# Schematic.net
KiCad netlist of a schematic drawn in Altium Designer
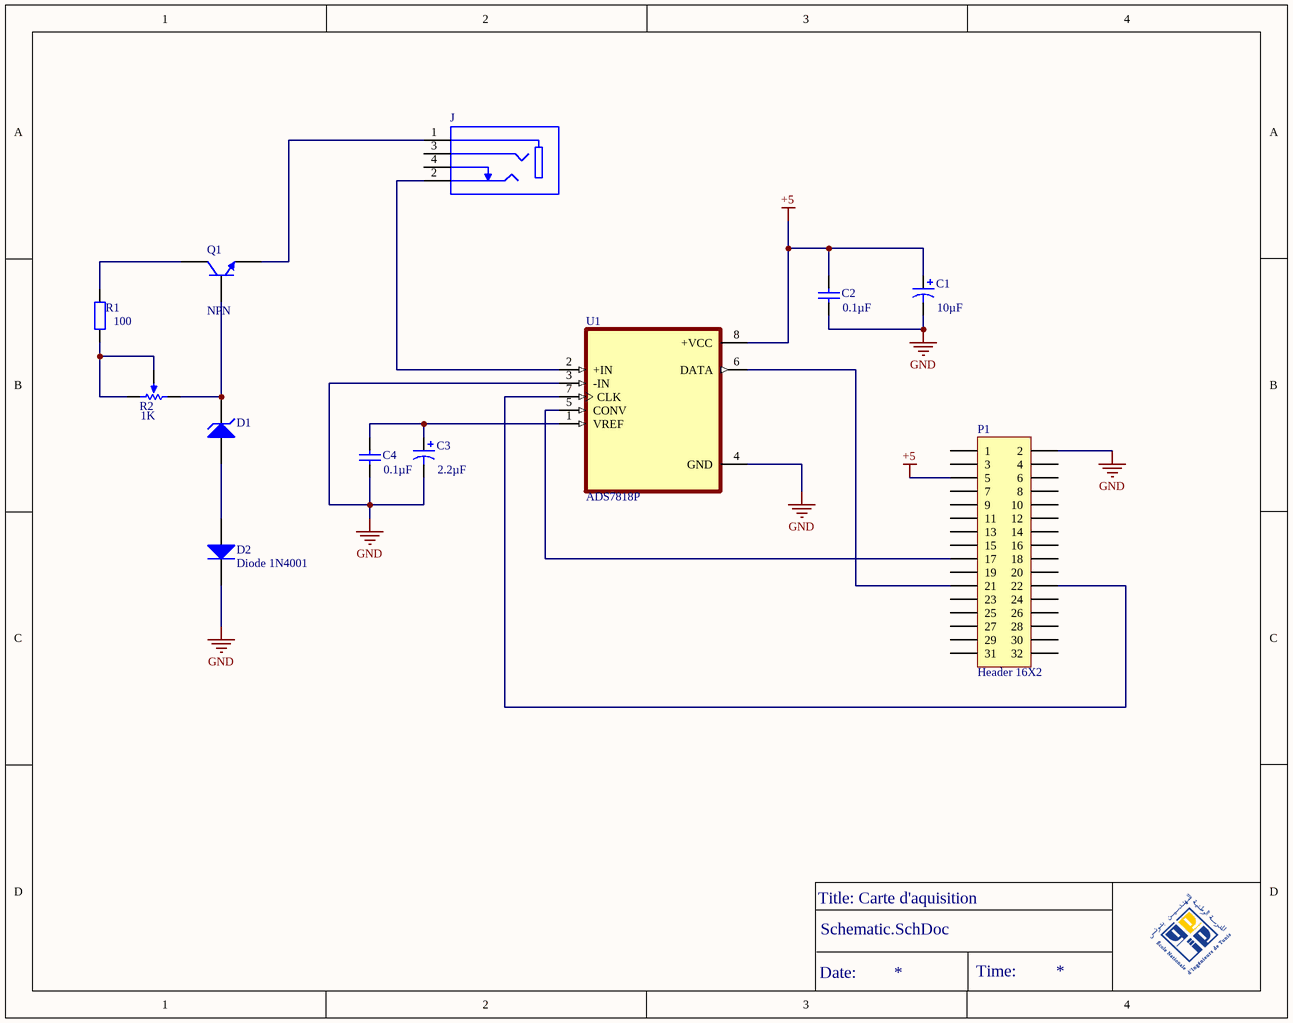
[diagram p0: Schematic.SchDoc]

(export (version "E")
  (design (tool "Eeschema 10.0.6"))
  (components
    (comp (ref "C1")
      (value "10µF")
      (footprint "RB7.6-15")
      (description "Polarized Capacitor (Radial)")
      (fields (field (name "Comment") "Cap Pol1") (field (name "PUBLISHER") "Altium Limited"))
      (libsource (lib "Miscellaneous Devices") (part "Cap Pol1"))
    )
    (comp (ref "C2")
      (value "0.1µF")
      (footprint "RAD-0.3")
      (description "Capacitor")
      (fields (field (name "Comment") "Cap") (field (name "PUBLISHER") "Altium Limited"))
      (libsource (lib "Miscellaneous Devices") (part "Cap"))
    )
    (comp (ref "C3")
      (value "2.2µF")
      (footprint "RB7.6-15")
      (description "Polarized Capacitor (Radial)")
      (fields (field (name "Comment") "Cap Pol1") (field (name "PUBLISHER") "Altium Limited"))
      (libsource (lib "Miscellaneous Devices") (part "Cap Pol1"))
    )
    (comp (ref "C4")
      (value "0.1µF")
      (footprint "RAD-0.3")
      (description "Capacitor")
      (fields (field (name "Comment") "Cap") (field (name "PUBLISHER") "Altium Limited"))
      (libsource (lib "Miscellaneous Devices") (part "Cap"))
    )
    (comp (ref "D1")
      (value "D Zener")
      (footprint "DIODE-0.7")
      (description "Zener Diode")
      (fields (field (name "PUBLISHER") "Altium Limited"))
      (libsource (lib "Miscellaneous Devices") (part "D Zener"))
    )
    (comp (ref "D2")
      (value "Diode 1N4001")
      (footprint "DO-41")
      (description "1 Amp General Purpose Rectifier")
      (fields (field (name "PUBLISHER") "Altium Limited"))
      (libsource (lib "Miscellaneous Devices") (part "Diode 1N4001"))
    )
    (comp (ref "J")
      (value "SJ1-3534N")
      (footprint "CUI_SJ1-3534N")
      (fields (field (name "MF") "CUI Devices"))
      (libsource (lib "SnapEDAsch") (part "SJ1-3534N"))
    )
    (comp (ref "P1")
      (value "Header 16X2")
      (footprint "HDR2X16")
      (description "Header, 16-Pin, Dual row")
      (fields (field (name "PUBLISHER") "Altium Limited"))
      (libsource (lib "Miscellaneous Connectors") (part "Header 16X2"))
    )
    (comp (ref "Q1")
      (value "NPN")
      (footprint "TO-226-AA")
      (description "NPN Bipolar Transistor")
      (fields (field (name "PUBLISHER") "Altium Limited"))
      (libsource (lib "Miscellaneous Devices") (part "NPN"))
    )
    (comp (ref "R1")
      (value "100")
      (footprint "AXIAL-0.4")
      (description "Resistor")
      (fields (field (name "Comment") "Res2"))
      (libsource (lib "Custom_Component") (part "Res2"))
    )
    (comp (ref "R2")
      (value "1K")
      (footprint "VR5")
      (description "Potentiometer")
      (fields (field (name "Comment") "RPot"))
      (libsource (lib "Custom_Component") (part "RPot"))
    )
    (comp (ref "U1")
      (value "ADS7818P")
      (footprint "DIP794W45P254L959H508Q8")
      (libsource (lib "ADS7818P") (part "ADS7818P"))
    )
  )
  (nets
    (net (code "1") (name "+5") (class "Default")
      (node (ref "C1") (pin "1") (pinfunction "1_1") (pintype "passive"))
      (node (ref "C2") (pin "2") (pinfunction "2_2") (pintype "passive"))
      (node (ref "P1") (pin "5") (pinfunction "5_5") (pintype "passive"))
      (node (ref "U1") (pin "8") (pinfunction "+VCC_8") (pintype "power_in"))
    )
    (net (code "2") (name "GND") (class "Default")
      (node (ref "C1") (pin "2") (pinfunction "2_2") (pintype "passive"))
      (node (ref "C2") (pin "1") (pinfunction "1_1") (pintype "passive"))
      (node (ref "C3") (pin "2") (pinfunction "2_2") (pintype "passive"))
      (node (ref "C4") (pin "1") (pinfunction "1_1") (pintype "passive"))
      (node (ref "D2") (pin "2") (pinfunction "K_2") (pintype "passive"))
      (node (ref "P1") (pin "2") (pinfunction "2_2") (pintype "passive"))
      (node (ref "U1") (pin "3") (pinfunction "-IN_3") (pintype "input"))
      (node (ref "U1") (pin "4") (pinfunction "GND_4") (pintype "power_in"))
    )
    (net (code "3") (name "Net-(D1-A)") (class "Default")
      (node (ref "D1") (pin "1") (pinfunction "A_1") (pintype "passive"))
      (node (ref "D2") (pin "1") (pinfunction "A_1") (pintype "passive"))
    )
    (net (code "4") (name "Net-(D1-K)") (class "Default")
      (node (ref "D1") (pin "2") (pinfunction "K_2") (pintype "passive"))
      (node (ref "Q1") (pin "2") (pinfunction "B_2") (pintype "passive"))
      (node (ref "R2") (pin "1") (pinfunction "TOP_1") (pintype "passive"))
    )
    (net (code "5") (name "Net-(Q1-C)") (class "Default")
      (node (ref "Q1") (pin "1") (pinfunction "C_1") (pintype "passive"))
      (node (ref "R1") (pin "2") (pinfunction "2_2") (pintype "passive"))
    )
    (net (code "6") (name "Net-(Q1-E)") (class "Default")
      (node (ref "J") (pin "1") (pinfunction "1_1") (pintype "passive"))
      (node (ref "Q1") (pin "3") (pinfunction "E_3") (pintype "passive"))
    )
    (net (code "7") (name "Net-(R2-BOT)") (class "Default")
      (node (ref "R1") (pin "1") (pinfunction "1_1") (pintype "passive"))
      (node (ref "R2") (pin "2") (pinfunction "BOT_2") (pintype "passive"))
      (node (ref "R2") (pin "3") (pinfunction "TAP_3") (pintype "passive"))
    )
    (net (code "8") (name "Net-(U1-+IN)") (class "Default")
      (node (ref "J") (pin "2") (pinfunction "2_2") (pintype "passive"))
      (node (ref "U1") (pin "2") (pinfunction "+IN_2") (pintype "input"))
    )
    (net (code "9") (name "Net-(U1-CLK)") (class "Default")
      (node (ref "P1") (pin "22") (pinfunction "22_22") (pintype "passive"))
      (node (ref "U1") (pin "7") (pinfunction "CLK_7") (pintype "input"))
    )
    (net (code "10") (name "Net-(U1-CONV)") (class "Default")
      (node (ref "P1") (pin "17") (pinfunction "17_17") (pintype "passive"))
      (node (ref "U1") (pin "5") (pinfunction "CONV_5") (pintype "input"))
    )
    (net (code "11") (name "Net-(U1-DATA)") (class "Default")
      (node (ref "P1") (pin "21") (pinfunction "21_21") (pintype "passive"))
      (node (ref "U1") (pin "6") (pinfunction "DATA_6") (pintype "output"))
    )
    (net (code "12") (name "Net-(U1-VREF)") (class "Default")
      (node (ref "C3") (pin "1") (pinfunction "1_1") (pintype "passive"))
      (node (ref "C4") (pin "2") (pinfunction "2_2") (pintype "passive"))
      (node (ref "U1") (pin "1") (pinfunction "VREF_1") (pintype "input"))
    )
    (net (code "13") (name "unconnected-(J-Pad3)") (class "Default")
      (node (ref "J") (pin "3") (pinfunction "3_3") (pintype "passive"))
    )
    (net (code "14") (name "unconnected-(J-Pad4)") (class "Default")
      (node (ref "J") (pin "4") (pinfunction "4_4") (pintype "passive"))
    )
    (net (code "15") (name "unconnected-(P1-Pad1)") (class "Default")
      (node (ref "P1") (pin "1") (pinfunction "1_1") (pintype "passive"))
    )
    (net (code "16") (name "unconnected-(P1-Pad3)") (class "Default")
      (node (ref "P1") (pin "3") (pinfunction "3_3") (pintype "passive"))
    )
    (net (code "17") (name "unconnected-(P1-Pad4)") (class "Default")
      (node (ref "P1") (pin "4") (pinfunction "4_4") (pintype "passive"))
    )
    (net (code "18") (name "unconnected-(P1-Pad6)") (class "Default")
      (node (ref "P1") (pin "6") (pinfunction "6_6") (pintype "passive"))
    )
    (net (code "19") (name "unconnected-(P1-Pad7)") (class "Default")
      (node (ref "P1") (pin "7") (pinfunction "7_7") (pintype "passive"))
    )
    (net (code "20") (name "unconnected-(P1-Pad8)") (class "Default")
      (node (ref "P1") (pin "8") (pinfunction "8_8") (pintype "passive"))
    )
    (net (code "21") (name "unconnected-(P1-Pad9)") (class "Default")
      (node (ref "P1") (pin "9") (pinfunction "9_9") (pintype "passive"))
    )
    (net (code "22") (name "unconnected-(P1-Pad10)") (class "Default")
      (node (ref "P1") (pin "10") (pinfunction "10_10") (pintype "passive"))
    )
    (net (code "23") (name "unconnected-(P1-Pad11)") (class "Default")
      (node (ref "P1") (pin "11") (pinfunction "11_11") (pintype "passive"))
    )
    (net (code "24") (name "unconnected-(P1-Pad12)") (class "Default")
      (node (ref "P1") (pin "12") (pinfunction "12_12") (pintype "passive"))
    )
    (net (code "25") (name "unconnected-(P1-Pad13)") (class "Default")
      (node (ref "P1") (pin "13") (pinfunction "13_13") (pintype "passive"))
    )
    (net (code "26") (name "unconnected-(P1-Pad14)") (class "Default")
      (node (ref "P1") (pin "14") (pinfunction "14_14") (pintype "passive"))
    )
    (net (code "27") (name "unconnected-(P1-Pad15)") (class "Default")
      (node (ref "P1") (pin "15") (pinfunction "15_15") (pintype "passive"))
    )
    (net (code "28") (name "unconnected-(P1-Pad16)") (class "Default")
      (node (ref "P1") (pin "16") (pinfunction "16_16") (pintype "passive"))
    )
    (net (code "29") (name "unconnected-(P1-Pad18)") (class "Default")
      (node (ref "P1") (pin "18") (pinfunction "18_18") (pintype "passive"))
    )
    (net (code "30") (name "unconnected-(P1-Pad19)") (class "Default")
      (node (ref "P1") (pin "19") (pinfunction "19_19") (pintype "passive"))
    )
    (net (code "31") (name "unconnected-(P1-Pad20)") (class "Default")
      (node (ref "P1") (pin "20") (pinfunction "20_20") (pintype "passive"))
    )
    (net (code "32") (name "unconnected-(P1-Pad23)") (class "Default")
      (node (ref "P1") (pin "23") (pinfunction "23_23") (pintype "passive"))
    )
    (net (code "33") (name "unconnected-(P1-Pad24)") (class "Default")
      (node (ref "P1") (pin "24") (pinfunction "24_24") (pintype "passive"))
    )
    (net (code "34") (name "unconnected-(P1-Pad25)") (class "Default")
      (node (ref "P1") (pin "25") (pinfunction "25_25") (pintype "passive"))
    )
    (net (code "35") (name "unconnected-(P1-Pad26)") (class "Default")
      (node (ref "P1") (pin "26") (pinfunction "26_26") (pintype "passive"))
    )
    (net (code "36") (name "unconnected-(P1-Pad27)") (class "Default")
      (node (ref "P1") (pin "27") (pinfunction "27_27") (pintype "passive"))
    )
    (net (code "37") (name "unconnected-(P1-Pad28)") (class "Default")
      (node (ref "P1") (pin "28") (pinfunction "28_28") (pintype "passive"))
    )
    (net (code "38") (name "unconnected-(P1-Pad29)") (class "Default")
      (node (ref "P1") (pin "29") (pinfunction "29_29") (pintype "passive"))
    )
    (net (code "39") (name "unconnected-(P1-Pad30)") (class "Default")
      (node (ref "P1") (pin "30") (pinfunction "30_30") (pintype "passive"))
    )
    (net (code "40") (name "unconnected-(P1-Pad31)") (class "Default")
      (node (ref "P1") (pin "31") (pinfunction "31_31") (pintype "passive"))
    )
    (net (code "41") (name "unconnected-(P1-Pad32)") (class "Default")
      (node (ref "P1") (pin "32") (pinfunction "32_32") (pintype "passive"))
    )
  )
)
